# CURRENT_SOURCE.net
KiCad netlist of a schematic drawn in Altium Designer
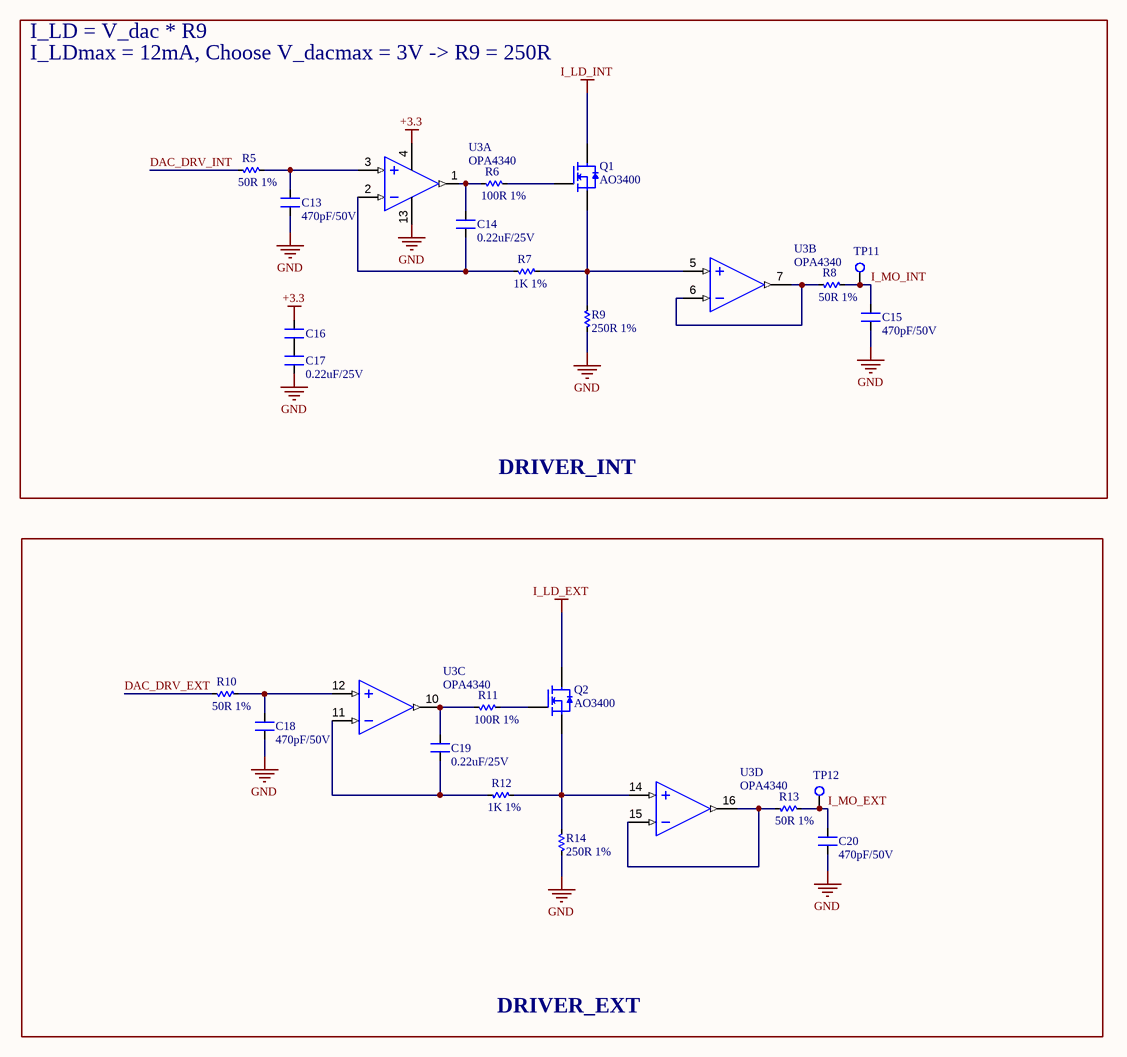
[diagram p0: CURRENT_SOURCE.SchDoc]

(export (version "E")
  (design (tool "Eeschema 10.0.6"))
  (components
    (comp (ref "C13")
      (value "470pF/50V")
      (footprint "SM-0603")
      (description "0603")
      (libsource (lib "Capacitors") (part "CM"))
    )
    (comp (ref "C14")
      (value "0.22uF/25V")
      (footprint "SM-0603")
      (description "0603")
      (libsource (lib "Capacitors") (part "CM"))
    )
    (comp (ref "C15")
      (value "470pF/50V")
      (footprint "SM-0603")
      (description "0603")
      (libsource (lib "Capacitors") (part "CM"))
    )
    (comp (ref "C16")
      (value "0.22uF/25V")
      (footprint "SM-0603")
      (description "0603")
      (libsource (lib "Capacitors") (part "CM"))
    )
    (comp (ref "C17")
      (value "0.22uF/25V")
      (footprint "SM-0603")
      (description "0603")
      (libsource (lib "Capacitors") (part "CM"))
    )
    (comp (ref "C18")
      (value "470pF/50V")
      (footprint "SM-0603")
      (description "0603")
      (libsource (lib "Capacitors") (part "CM"))
    )
    (comp (ref "C19")
      (value "0.22uF/25V")
      (footprint "SM-0603")
      (description "0603")
      (libsource (lib "Capacitors") (part "CM"))
    )
    (comp (ref "C20")
      (value "470pF/50V")
      (footprint "SM-0603")
      (description "0603")
      (libsource (lib "Capacitors") (part "CM"))
    )
    (comp (ref "Q1") (value "AO3400") (footprint "SOT23-132") (libsource (lib "Library") (part "FET-N")))
    (comp (ref "Q2") (value "AO3400") (footprint "SOT23-132") (libsource (lib "Library") (part "FET-N")))
    (comp (ref "R5")
      (value "50R 1%")
      (footprint "RES-SMD-0603")
      (description "0603")
      (fields
        (field (name "MANUFACTURER") "Generic Components")
        (field (name "PUBLISHER") "Altium Hobart Technology Centre")
      )
      (libsource (lib "Library") (part "Res-SMD"))
    )
    (comp (ref "R6")
      (value "100R 1%")
      (footprint "RES-SMD-0603")
      (description "0603")
      (fields
        (field (name "MANUFACTURER") "Generic Components")
        (field (name "PUBLISHER") "Altium Hobart Technology Centre")
      )
      (libsource (lib "Library") (part "Res-SMD"))
    )
    (comp (ref "R7")
      (value "1K 1%")
      (footprint "RES-SMD-0603")
      (description "0603")
      (fields
        (field (name "MANUFACTURER") "Generic Components")
        (field (name "PUBLISHER") "Altium Hobart Technology Centre")
      )
      (libsource (lib "Library") (part "Res-SMD"))
    )
    (comp (ref "R8")
      (value "50R 1%")
      (footprint "RES-SMD-0603")
      (description "0603")
      (fields
        (field (name "MANUFACTURER") "Generic Components")
        (field (name "PUBLISHER") "Altium Hobart Technology Centre")
      )
      (libsource (lib "Library") (part "Res-SMD"))
    )
    (comp (ref "R9")
      (value "250R 1%")
      (footprint "RES-SMD-1206")
      (description "1206")
      (fields
        (field (name "MANUFACTURER") "Generic Components")
        (field (name "PUBLISHER") "Altium Hobart Technology Centre")
      )
      (libsource (lib "Library") (part "Res-SMD"))
    )
    (comp (ref "R10")
      (value "50R 1%")
      (footprint "RES-SMD-0603")
      (description "0603")
      (fields
        (field (name "MANUFACTURER") "Generic Components")
        (field (name "PUBLISHER") "Altium Hobart Technology Centre")
      )
      (libsource (lib "Library") (part "Res-SMD"))
    )
    (comp (ref "R11")
      (value "100R 1%")
      (footprint "RES-SMD-0603")
      (description "0603")
      (fields
        (field (name "MANUFACTURER") "Generic Components")
        (field (name "PUBLISHER") "Altium Hobart Technology Centre")
      )
      (libsource (lib "Library") (part "Res-SMD"))
    )
    (comp (ref "R12")
      (value "1K 1%")
      (footprint "RES-SMD-0603")
      (description "0603")
      (fields
        (field (name "MANUFACTURER") "Generic Components")
        (field (name "PUBLISHER") "Altium Hobart Technology Centre")
      )
      (libsource (lib "Library") (part "Res-SMD"))
    )
    (comp (ref "R13")
      (value "50R 1%")
      (footprint "RES-SMD-0603")
      (description "0603")
      (fields
        (field (name "MANUFACTURER") "Generic Components")
        (field (name "PUBLISHER") "Altium Hobart Technology Centre")
      )
      (libsource (lib "Library") (part "Res-SMD"))
    )
    (comp (ref "R14")
      (value "250R 1%")
      (footprint "RES-SMD-1206")
      (description "0603")
      (fields
        (field (name "MANUFACTURER") "Generic Components")
        (field (name "PUBLISHER") "Altium Hobart Technology Centre")
      )
      (libsource (lib "Library") (part "Res-SMD"))
    )
    (comp (ref "TP11")
      (value "Test_Point")
      (footprint "TESTPOINT")
      (libsource (lib "Library_HUNG") (part "Test_Point"))
    )
    (comp (ref "TP12")
      (value "Test_Point")
      (footprint "TESTPOINT")
      (libsource (lib "Library_HUNG") (part "Test_Point"))
    )
    (comp (ref "U3")
      (value "OPA4340")
      (footprint "SSOP16")
      (description "IC CMOS 4 CIRCUIT 16SSOP")
      (libsource (lib "Library") (part "OPA4340"))
    )
  )
  (nets
    (net (code "1") (name "+3.3") (class "Default")
      (node (ref "C16") (pin "2") (pinfunction "2_2") (pintype "passive"))
      (node (ref "U3") (pin "4") (pinfunction "+V_4") (pintype "passive"))
    )
    (net (code "2") (name "/DAC_DRV_EXT") (class "Default")
      (node (ref "R10") (pin "1") (pinfunction "1_1") (pintype "passive"))
    )
    (net (code "3") (name "/DAC_DRV_INT") (class "Default")
      (node (ref "R5") (pin "1") (pinfunction "1_1") (pintype "passive"))
    )
    (net (code "4") (name "/I_MO_EXT") (class "Default")
      (node (ref "C20") (pin "2") (pinfunction "2_2") (pintype "passive"))
      (node (ref "R13") (pin "2") (pinfunction "2_2") (pintype "passive"))
      (node (ref "TP12") (pin "1") (pintype "power_in"))
    )
    (net (code "5") (name "/I_MO_INT") (class "Default")
      (node (ref "C15") (pin "2") (pinfunction "2_2") (pintype "passive"))
      (node (ref "R8") (pin "2") (pinfunction "2_2") (pintype "passive"))
      (node (ref "TP11") (pin "1") (pintype "power_in"))
    )
    (net (code "6") (name "GND") (class "Default")
      (node (ref "C13") (pin "1") (pinfunction "1_1") (pintype "passive"))
      (node (ref "C15") (pin "1") (pinfunction "1_1") (pintype "passive"))
      (node (ref "C17") (pin "1") (pinfunction "1_1") (pintype "passive"))
      (node (ref "C18") (pin "1") (pinfunction "1_1") (pintype "passive"))
      (node (ref "C20") (pin "1") (pinfunction "1_1") (pintype "passive"))
      (node (ref "R14") (pin "1") (pinfunction "1_1") (pintype "passive"))
      (node (ref "R9") (pin "1") (pinfunction "1_1") (pintype "passive"))
      (node (ref "U3") (pin "13") (pinfunction "-V_13") (pintype "passive"))
    )
    (net (code "7") (name "I_LD_EXT") (class "Default") (node (ref "Q2") (pin "3") (pintype "power_in")))
    (net (code "8") (name "I_LD_INT") (class "Default") (node (ref "Q1") (pin "3") (pintype "power_in")))
    (net (code "9") (name "Net-(C16-Pad1)") (class "Default")
      (node (ref "C16") (pin "1") (pinfunction "1_1") (pintype "passive"))
      (node (ref "C17") (pin "2") (pinfunction "2_2") (pintype "passive"))
    )
    (net (code "10") (name "Net-(Q1-Pad1)") (class "Default")
      (node (ref "Q1") (pin "1") (pintype "power_in"))
      (node (ref "R6") (pin "2") (pinfunction "2_2") (pintype "passive"))
    )
    (net (code "11") (name "Net-(Q2-Pad1)") (class "Default")
      (node (ref "Q2") (pin "1") (pintype "power_in"))
      (node (ref "R11") (pin "2") (pinfunction "2_2") (pintype "passive"))
    )
    (net (code "12") (name "Net-(U3A-IN+)") (class "Default")
      (node (ref "C13") (pin "2") (pinfunction "2_2") (pintype "passive"))
      (node (ref "R5") (pin "2") (pinfunction "2_2") (pintype "passive"))
      (node (ref "U3") (pin "3") (pinfunction "IN+_3") (pintype "input"))
    )
    (net (code "13") (name "Net-(U3A-IN-)") (class "Default")
      (node (ref "C14") (pin "1") (pinfunction "1_1") (pintype "passive"))
      (node (ref "R7") (pin "1") (pinfunction "1_1") (pintype "passive"))
      (node (ref "U3") (pin "2") (pinfunction "IN-_2") (pintype "input"))
    )
    (net (code "14") (name "Net-(U3A-OUT)") (class "Default")
      (node (ref "C14") (pin "2") (pinfunction "2_2") (pintype "passive"))
      (node (ref "R6") (pin "1") (pinfunction "1_1") (pintype "passive"))
      (node (ref "U3") (pin "1") (pinfunction "OUT_1") (pintype "output"))
    )
    (net (code "15") (name "Net-(U3B-IN+)") (class "Default")
      (node (ref "Q1") (pin "2") (pintype "power_in"))
      (node (ref "R7") (pin "2") (pinfunction "2_2") (pintype "passive"))
      (node (ref "R9") (pin "2") (pinfunction "2_2") (pintype "passive"))
      (node (ref "U3") (pin "5") (pinfunction "IN+_5") (pintype "input"))
    )
    (net (code "16") (name "Net-(U3B-IN-)") (class "Default")
      (node (ref "R8") (pin "1") (pinfunction "1_1") (pintype "passive"))
      (node (ref "U3") (pin "6") (pinfunction "IN-_6") (pintype "input"))
      (node (ref "U3") (pin "7") (pinfunction "OUT_7") (pintype "output"))
    )
    (net (code "17") (name "Net-(U3C-IN+)") (class "Default")
      (node (ref "C18") (pin "2") (pinfunction "2_2") (pintype "passive"))
      (node (ref "R10") (pin "2") (pinfunction "2_2") (pintype "passive"))
      (node (ref "U3") (pin "12") (pinfunction "IN+_12") (pintype "input"))
    )
    (net (code "18") (name "Net-(U3C-IN-)") (class "Default")
      (node (ref "C19") (pin "1") (pinfunction "1_1") (pintype "passive"))
      (node (ref "R12") (pin "1") (pinfunction "1_1") (pintype "passive"))
      (node (ref "U3") (pin "11") (pinfunction "IN-_11") (pintype "input"))
    )
    (net (code "19") (name "Net-(U3C-OUT)") (class "Default")
      (node (ref "C19") (pin "2") (pinfunction "2_2") (pintype "passive"))
      (node (ref "R11") (pin "1") (pinfunction "1_1") (pintype "passive"))
      (node (ref "U3") (pin "10") (pinfunction "OUT_10") (pintype "output"))
    )
    (net (code "20") (name "Net-(U3D-IN+)") (class "Default")
      (node (ref "Q2") (pin "2") (pintype "power_in"))
      (node (ref "R12") (pin "2") (pinfunction "2_2") (pintype "passive"))
      (node (ref "R14") (pin "2") (pinfunction "2_2") (pintype "passive"))
      (node (ref "U3") (pin "14") (pinfunction "IN+_14") (pintype "input"))
    )
    (net (code "21") (name "Net-(U3D-IN-)") (class "Default")
      (node (ref "R13") (pin "1") (pinfunction "1_1") (pintype "passive"))
      (node (ref "U3") (pin "15") (pinfunction "IN-_15") (pintype "input"))
      (node (ref "U3") (pin "16") (pinfunction "OUT_16") (pintype "output"))
    )
  )
)
